# m1k_analog_mux-4052.net
KiCad netlist of a schematic drawn in EAGLE
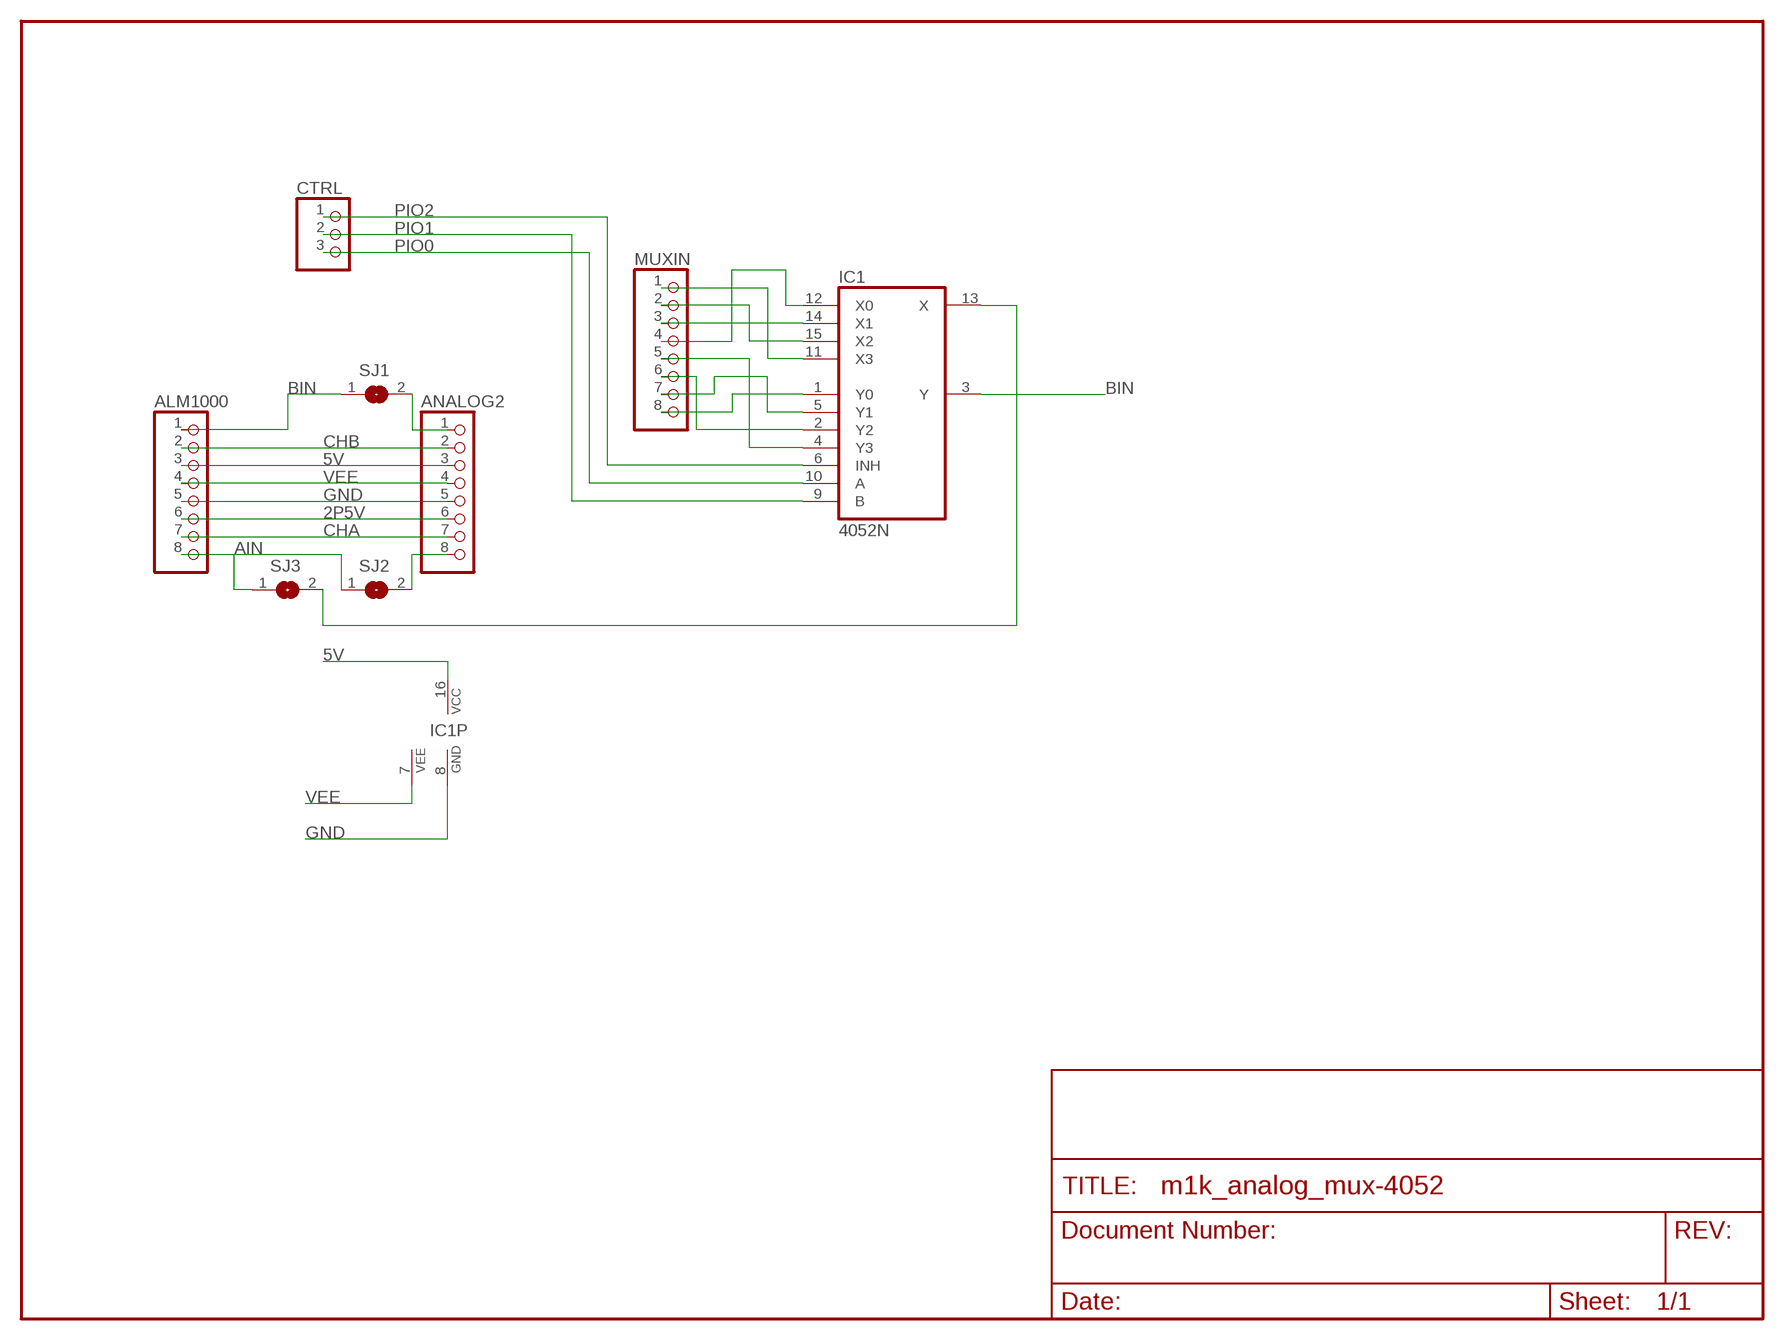
[diagram p0: schematic, sheet 1]

(export (version "E")
  (design (tool "Eeschema 10.0.6"))
  (components
    (comp (ref "ALM1000")
      (value "PINHD-1X8")
      (footprint "eagle-import:1X08")
      (libsource (lib "eagle-import") (part "PINHD-1X8"))
    )
    (comp (ref "ANALOG2")
      (value "PINHD-1X8")
      (footprint "eagle-import:1X08")
      (libsource (lib "eagle-import") (part "PINHD-1X8"))
    )
    (comp (ref "CTRL")
      (value "PINHD-1X3")
      (footprint "eagle-import:1X03")
      (libsource (lib "eagle-import") (part "PINHD-1X3"))
    )
    (comp (ref "IC1")
      (value "4052N")
      (footprint "eagle-import:DIL16")
      (libsource (lib "eagle-import") (part "4052N"))
    )
    (comp (ref "MUXIN")
      (value "PINHD-1X8")
      (footprint "eagle-import:1X08")
      (libsource (lib "eagle-import") (part "PINHD-1X8"))
    )
    (comp (ref "SJ1") (value "SJ") (footprint "eagle-import:SJ") (libsource (lib "eagle-import") (part "SJ")))
    (comp (ref "SJ2") (value "SJ") (footprint "eagle-import:SJ") (libsource (lib "eagle-import") (part "SJ")))
    (comp (ref "SJ3") (value "SJ") (footprint "eagle-import:SJ") (libsource (lib "eagle-import") (part "SJ")))
  )
  (nets
    (net (code "1") (name "/2P5V") (class "Default")
      (node (ref "ALM1000") (pin "6") (pinfunction "6_6") (pintype "passive"))
      (node (ref "ANALOG2") (pin "6") (pinfunction "6_6") (pintype "passive"))
    )
    (net (code "2") (name "/5V") (class "Default")
      (node (ref "ALM1000") (pin "3") (pinfunction "3_3") (pintype "passive"))
      (node (ref "ANALOG2") (pin "3") (pinfunction "3_3") (pintype "passive"))
      (node (ref "IC1") (pin "16") (pinfunction "VCC_16") (pintype "power_in"))
    )
    (net (code "3") (name "/AIN") (class "Default")
      (node (ref "ALM1000") (pin "8") (pinfunction "8_8") (pintype "passive"))
      (node (ref "SJ2") (pin "1") (pinfunction "1_1") (pintype "passive"))
      (node (ref "SJ3") (pin "1") (pinfunction "1_1") (pintype "passive"))
    )
    (net (code "4") (name "/BIN") (class "Default")
      (node (ref "ALM1000") (pin "1") (pinfunction "1_1") (pintype "passive"))
      (node (ref "IC1") (pin "3") (pinfunction "Y_3") (pintype "bidirectional"))
      (node (ref "SJ1") (pin "1") (pinfunction "1_1") (pintype "passive"))
    )
    (net (code "5") (name "/CHA") (class "Default")
      (node (ref "ALM1000") (pin "7") (pinfunction "7_7") (pintype "passive"))
      (node (ref "ANALOG2") (pin "7") (pinfunction "7_7") (pintype "passive"))
    )
    (net (code "6") (name "/CHB") (class "Default")
      (node (ref "ALM1000") (pin "2") (pinfunction "2_2") (pintype "passive"))
      (node (ref "ANALOG2") (pin "2") (pinfunction "2_2") (pintype "passive"))
    )
    (net (code "7") (name "/GND") (class "Default")
      (node (ref "ALM1000") (pin "5") (pinfunction "5_5") (pintype "passive"))
      (node (ref "ANALOG2") (pin "5") (pinfunction "5_5") (pintype "passive"))
      (node (ref "IC1") (pin "8") (pinfunction "GND_8") (pintype "power_in"))
    )
    (net (code "8") (name "/PIO0") (class "Default")
      (node (ref "CTRL") (pin "3") (pinfunction "3_3") (pintype "passive"))
      (node (ref "IC1") (pin "10") (pinfunction "A_10") (pintype "input"))
    )
    (net (code "9") (name "/PIO1") (class "Default")
      (node (ref "CTRL") (pin "2") (pinfunction "2_2") (pintype "passive"))
      (node (ref "IC1") (pin "9") (pinfunction "B_9") (pintype "input"))
    )
    (net (code "10") (name "/PIO2") (class "Default")
      (node (ref "CTRL") (pin "1") (pinfunction "1_1") (pintype "passive"))
      (node (ref "IC1") (pin "6") (pinfunction "INH_6") (pintype "input"))
    )
    (net (code "11") (name "/VEE") (class "Default")
      (node (ref "ALM1000") (pin "4") (pinfunction "4_4") (pintype "passive"))
      (node (ref "ANALOG2") (pin "4") (pinfunction "4_4") (pintype "passive"))
      (node (ref "IC1") (pin "7") (pinfunction "VEE_7") (pintype "power_in"))
    )
    (net (code "12") (name "Net-(ANALOG2-Pad1)") (class "Default")
      (node (ref "ANALOG2") (pin "1") (pinfunction "1_1") (pintype "passive"))
      (node (ref "SJ1") (pin "2") (pinfunction "2_2") (pintype "passive"))
    )
    (net (code "13") (name "Net-(ANALOG2-Pad8)") (class "Default")
      (node (ref "ANALOG2") (pin "8") (pinfunction "8_8") (pintype "passive"))
      (node (ref "SJ2") (pin "2") (pinfunction "2_2") (pintype "passive"))
    )
    (net (code "14") (name "Net-(IC1A-X)") (class "Default")
      (node (ref "IC1") (pin "13") (pinfunction "X_13") (pintype "bidirectional"))
      (node (ref "SJ3") (pin "2") (pinfunction "2_2") (pintype "passive"))
    )
    (net (code "15") (name "Net-(IC1A-X0)") (class "Default")
      (node (ref "IC1") (pin "12") (pinfunction "X0_12") (pintype "bidirectional"))
      (node (ref "MUXIN") (pin "4") (pinfunction "4_4") (pintype "passive"))
    )
    (net (code "16") (name "Net-(IC1A-X1)") (class "Default")
      (node (ref "IC1") (pin "14") (pinfunction "X1_14") (pintype "bidirectional"))
      (node (ref "MUXIN") (pin "3") (pinfunction "3_3") (pintype "passive"))
    )
    (net (code "17") (name "Net-(IC1A-X2)") (class "Default")
      (node (ref "IC1") (pin "15") (pinfunction "X2_15") (pintype "bidirectional"))
      (node (ref "MUXIN") (pin "2") (pinfunction "2_2") (pintype "passive"))
    )
    (net (code "18") (name "Net-(IC1A-X3)") (class "Default")
      (node (ref "IC1") (pin "11") (pinfunction "X3_11") (pintype "bidirectional"))
      (node (ref "MUXIN") (pin "1") (pinfunction "1_1") (pintype "passive"))
    )
    (net (code "19") (name "Net-(IC1A-Y0)") (class "Default")
      (node (ref "IC1") (pin "1") (pinfunction "Y0_1") (pintype "bidirectional"))
      (node (ref "MUXIN") (pin "8") (pinfunction "8_8") (pintype "passive"))
    )
    (net (code "20") (name "Net-(IC1A-Y1)") (class "Default")
      (node (ref "IC1") (pin "5") (pinfunction "Y1_5") (pintype "bidirectional"))
      (node (ref "MUXIN") (pin "7") (pinfunction "7_7") (pintype "passive"))
    )
    (net (code "21") (name "Net-(IC1A-Y2)") (class "Default")
      (node (ref "IC1") (pin "2") (pinfunction "Y2_2") (pintype "bidirectional"))
      (node (ref "MUXIN") (pin "6") (pinfunction "6_6") (pintype "passive"))
    )
    (net (code "22") (name "Net-(IC1A-Y3)") (class "Default")
      (node (ref "IC1") (pin "4") (pinfunction "Y3_4") (pintype "bidirectional"))
      (node (ref "MUXIN") (pin "5") (pinfunction "5_5") (pintype "passive"))
    )
  )
)
